# ads1115-reference_easyeda.net
KiCad netlist of a schematic drawn in EasyEDA
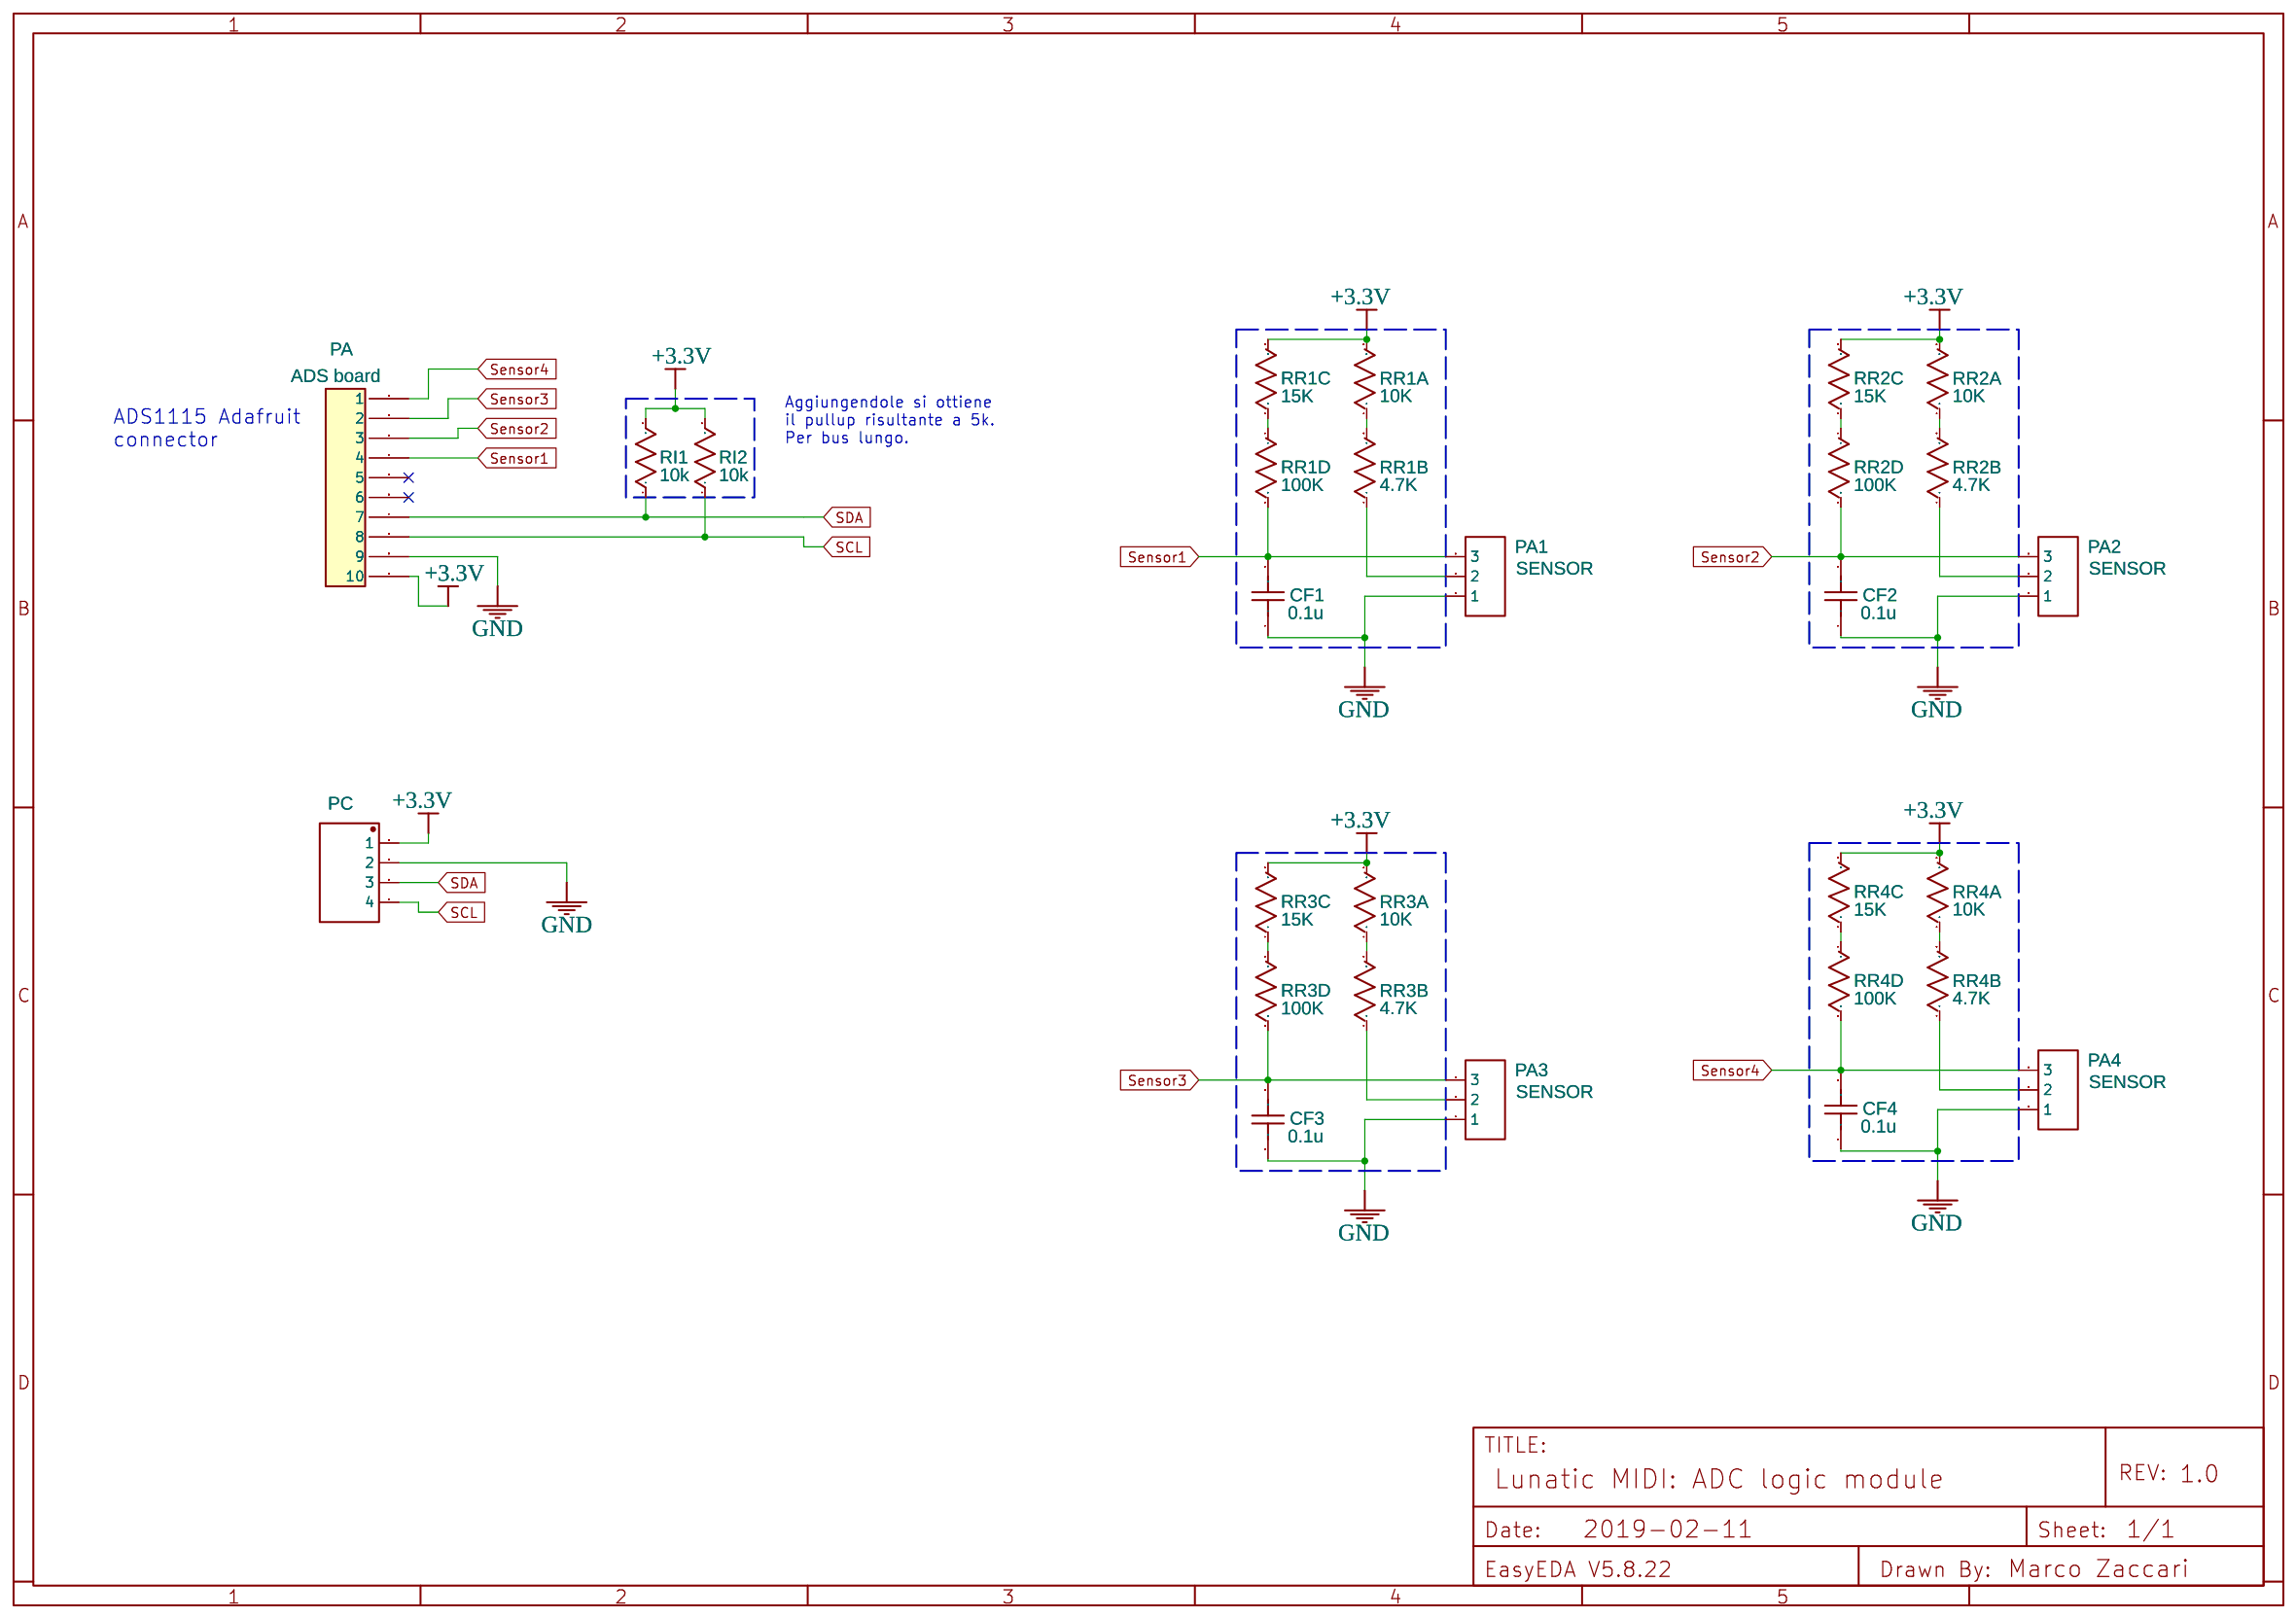
[diagram p0: ADC logic]
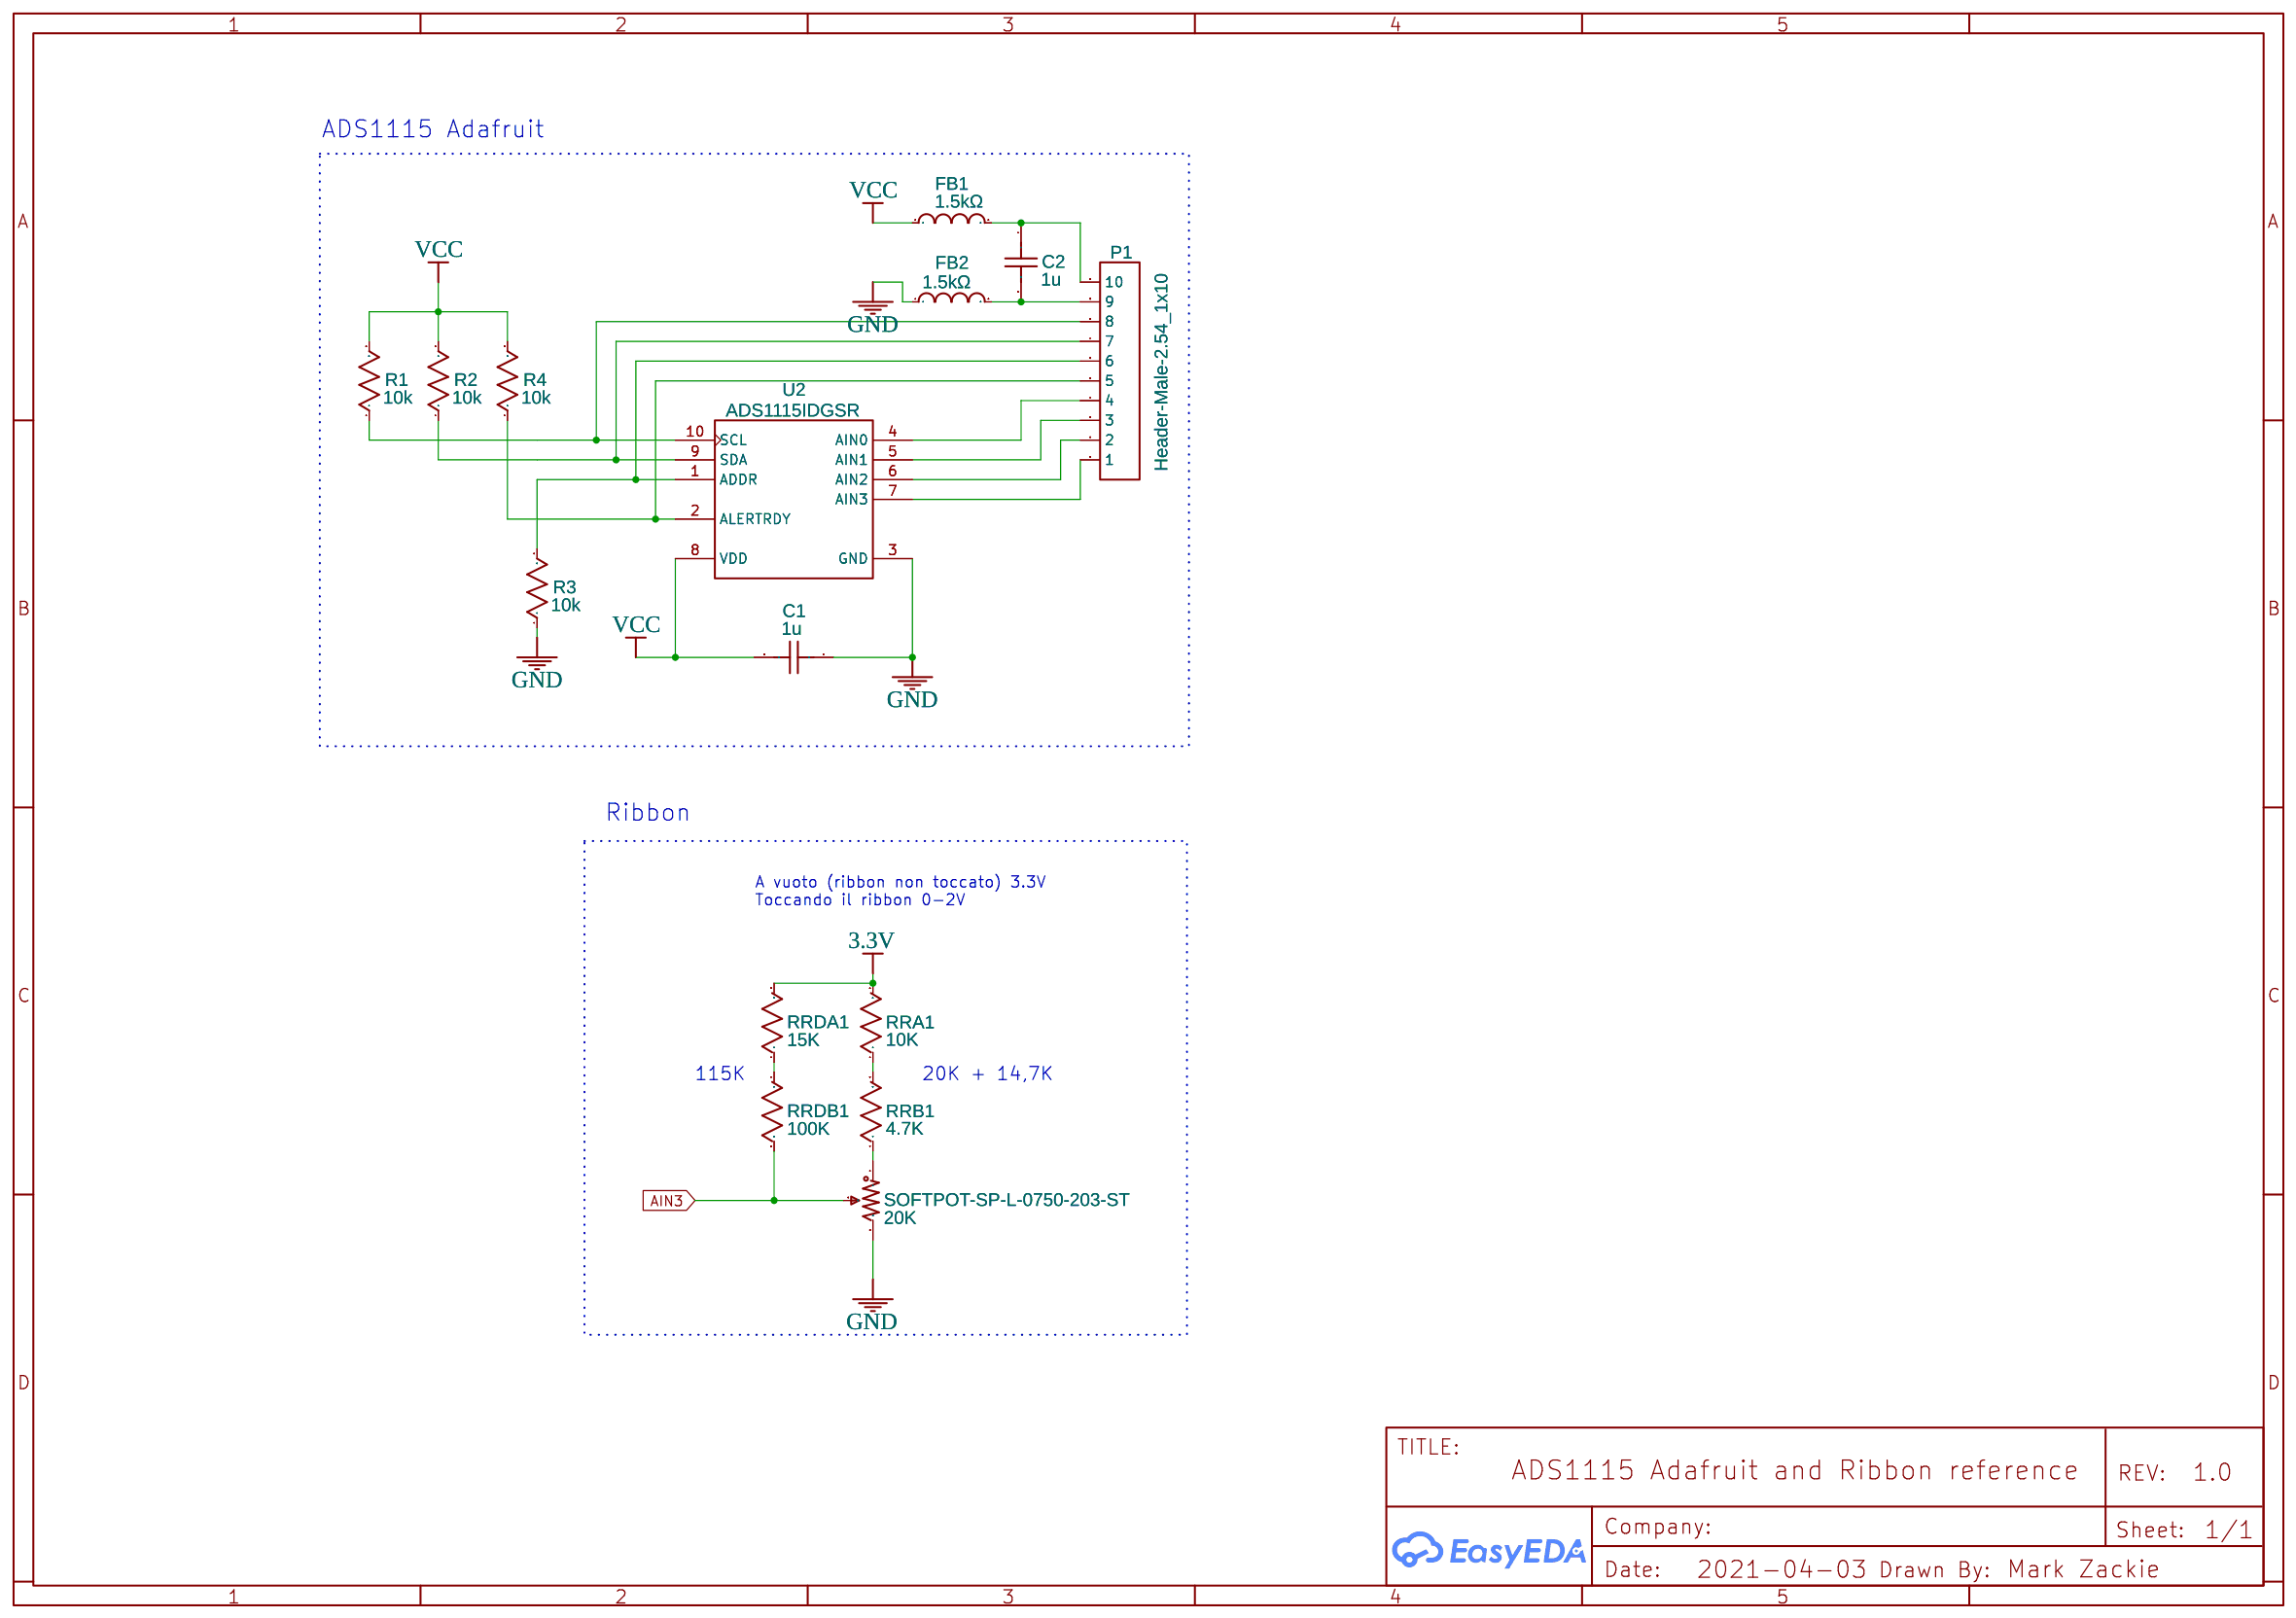
[diagram p1: ADS1115 Adafruit and Ribbon (reference)]

(export (version "E")
  (design (tool "Eeschema 10.0.6"))
  (components
    (comp (ref "CF1")
      (value "0.1u")
      (fields (field (name "BOM_Manufacturer Part") "?"))
      (libsource (lib "") (part "Cap_RAD-0.1_US"))
    )
    (comp (ref "CF2")
      (value "0.1u")
      (fields (field (name "BOM_Manufacturer Part") "?"))
      (libsource (lib "") (part "Cap_RAD-0.1_US"))
    )
    (comp (ref "CF3")
      (value "0.1u")
      (fields (field (name "BOM_Manufacturer Part") "?"))
      (libsource (lib "") (part "Cap_RAD-0.1_US"))
    )
    (comp (ref "CF4")
      (value "0.1u")
      (fields (field (name "BOM_Manufacturer Part") "?"))
      (libsource (lib "") (part "Cap_RAD-0.1_US"))
    )
    (comp (ref "PA")
      (value "ADS board")
      (fields
        (field (name "BOM_Manufacturer Part") "Header-Female-1.27_1x10")
        (field (name "BOM_Supplier Part") "C29357")
      )
      (libsource (lib "") (part "Unknown_180_240"))
    )
    (comp (ref "PA1")
      (value "SENSOR")
      (fields
        (field (name "BOM_Manufacturer Part") "Header2.54mm 1*3P")
        (field (name "BOM_Supplier Part") "C49257")
      )
      (libsource (lib "") (part "Unknown_740_285"))
    )
    (comp (ref "PA2")
      (value "SENSOR")
      (fields
        (field (name "BOM_Manufacturer Part") "Header2.54mm 1*3P")
        (field (name "BOM_Supplier Part") "C49257")
      )
      (libsource (lib "") (part "Unknown_1030_285"))
    )
    (comp (ref "PA3")
      (value "SENSOR")
      (fields
        (field (name "BOM_Manufacturer Part") "Header2.54mm 1*3P")
        (field (name "BOM_Supplier Part") "C49257")
      )
      (libsource (lib "") (part "Unknown_740_550"))
    )
    (comp (ref "PA4")
      (value "SENSOR")
      (fields
        (field (name "BOM_Manufacturer Part") "Header2.54mm 1*3P")
        (field (name "BOM_Supplier Part") "C49257")
      )
      (libsource (lib "") (part "Unknown_1030_545"))
    )
    (comp (ref "PC")
      (value "Header-Male-2.54_1x4")
      (fields
        (field (name "BOM_Manufacturer Part") "210S-1*4P L=11.6MMGold-plated black")
        (field (name "BOM_Supplier Part") "C124378")
      )
      (libsource (lib "") (part "Unknown_175_435"))
    )
    (comp (ref "RI1")
      (value "10k")
      (fields (field (name "BOM_Manufacturer Part") "?"))
      (libsource (lib "") (part "Res_AXIAL-0.3(1/8W)_US_9"))
    )
    (comp (ref "RI2")
      (value "10k")
      (fields (field (name "BOM_Manufacturer Part") "?"))
      (libsource (lib "") (part "Res_AXIAL-0.3(1/8W)_US_9"))
    )
    (comp (ref "RR1A")
      (value "10K")
      (fields (field (name "BOM_Manufacturer Part") "?"))
      (libsource (lib "") (part "Res_AXIAL-0.3(1/8W)_US_11"))
    )
    (comp (ref "RR1B")
      (value "4.7K")
      (fields (field (name "BOM_Manufacturer Part") "?"))
      (libsource (lib "") (part "Res_AXIAL-0.3(1/8W)_US_12"))
    )
    (comp (ref "RR1C")
      (value "15K")
      (fields (field (name "BOM_Manufacturer Part") "?"))
      (libsource (lib "") (part "Res_AXIAL-0.3(1/8W)_US_6"))
    )
    (comp (ref "RR1D")
      (value "100K")
      (fields (field (name "BOM_Manufacturer Part") "?"))
      (libsource (lib "") (part "Res_AXIAL-0.3(1/8W)_US_4"))
    )
    (comp (ref "RR2A")
      (value "10K")
      (fields (field (name "BOM_Manufacturer Part") "?"))
      (libsource (lib "") (part "Res_AXIAL-0.3(1/8W)_US_1"))
    )
    (comp (ref "RR2B")
      (value "4.7K")
      (fields (field (name "BOM_Manufacturer Part") "?"))
      (libsource (lib "") (part "Res_AXIAL-0.3(1/8W)_US_2"))
    )
    (comp (ref "RR2C")
      (value "15K")
      (fields (field (name "BOM_Manufacturer Part") "?"))
      (libsource (lib "") (part "Res_AXIAL-0.3(1/8W)_US_13"))
    )
    (comp (ref "RR2D")
      (value "100K")
      (fields (field (name "BOM_Manufacturer Part") "?"))
      (libsource (lib "") (part "Res_AXIAL-0.3(1/8W)_US"))
    )
    (comp (ref "RR3A")
      (value "10K")
      (fields (field (name "BOM_Manufacturer Part") "?"))
      (libsource (lib "") (part "Res_AXIAL-0.3(1/8W)_US_5"))
    )
    (comp (ref "RR3B")
      (value "4.7K")
      (fields (field (name "BOM_Manufacturer Part") "?"))
      (libsource (lib "") (part "Res_AXIAL-0.3(1/8W)_US_16"))
    )
    (comp (ref "RR3C")
      (value "15K")
      (fields (field (name "BOM_Manufacturer Part") "?"))
      (libsource (lib "") (part "Res_AXIAL-0.3(1/8W)_US_7"))
    )
    (comp (ref "RR3D")
      (value "100K")
      (fields (field (name "BOM_Manufacturer Part") "?"))
      (libsource (lib "") (part "Res_AXIAL-0.3(1/8W)_US_3"))
    )
    (comp (ref "RR4A")
      (value "10K")
      (fields (field (name "BOM_Manufacturer Part") "?"))
      (libsource (lib "") (part "Res_AXIAL-0.3(1/8W)_US_14"))
    )
    (comp (ref "RR4B")
      (value "4.7K")
      (fields (field (name "BOM_Manufacturer Part") "?"))
      (libsource (lib "") (part "Res_AXIAL-0.3(1/8W)_US_8"))
    )
    (comp (ref "RR4C")
      (value "15K")
      (fields (field (name "BOM_Manufacturer Part") "?"))
      (libsource (lib "") (part "Res_AXIAL-0.3(1/8W)_US_15"))
    )
    (comp (ref "RR4D")
      (value "100K")
      (fields (field (name "BOM_Manufacturer Part") "?"))
      (libsource (lib "") (part "Res_AXIAL-0.3(1/8W)_US_10"))
    )
    (comp (ref "C1")
      (value "1u")
      (fields (field (name "BOM_Manufacturer Part") "?"))
      (libsource (lib "") (part "Cap_RAD-0.1_US"))
    )
    (comp (ref "C2")
      (value "1u")
      (fields (field (name "BOM_Manufacturer Part") "?"))
      (libsource (lib "") (part "Cap_RAD-0.1_US_1"))
    )
    (comp (ref "FB1")
      (value "1.5kΩ")
      (fields
        (field (name "BOM_Manufacturer Part") "MMZ2012Y152B")
        (field (name "BOM_Supplier Part") "C21517")
      )
      (libsource (lib "") (part "MMZ2012Y152B"))
    )
    (comp (ref "FB2")
      (value "1.5kΩ")
      (fields
        (field (name "BOM_Manufacturer Part") "MMZ2012Y152B")
        (field (name "BOM_Supplier Part") "C21517")
      )
      (libsource (lib "") (part "MMZ2012Y152B"))
    )
    (comp (ref "P1")
      (value "Header-Male-2.54_1x10")
      (fields
        (field (name "BOM_Manufacturer Part") "Headers  Pins2.54mm1*10P")
        (field (name "BOM_Supplier Part") "C57369")
      )
      (libsource (lib "") (part "Unknown_555_-625"))
    )
    (comp (ref "R1")
      (value "10k")
      (fields (field (name "BOM_Manufacturer Part") "?"))
      (libsource (lib "") (part "Res_AXIAL-0.3(1/8W)_US"))
    )
    (comp (ref "R2")
      (value "10k")
      (fields (field (name "BOM_Manufacturer Part") "?"))
      (libsource (lib "") (part "Res_AXIAL-0.3(1/8W)_US"))
    )
    (comp (ref "R3")
      (value "10k")
      (fields (field (name "BOM_Manufacturer Part") "?"))
      (libsource (lib "") (part "Res_AXIAL-0.3(1/8W)_US"))
    )
    (comp (ref "R4")
      (value "10k")
      (fields (field (name "BOM_Manufacturer Part") "?"))
      (libsource (lib "") (part "Res_AXIAL-0.3(1/8W)_US"))
    )
    (comp (ref "RRA1")
      (value "10K")
      (fields (field (name "BOM_Manufacturer Part") "?"))
      (libsource (lib "") (part "Res_AXIAL-0.3(1/8W)_US_3"))
    )
    (comp (ref "RRB1")
      (value "4.7K")
      (fields (field (name "BOM_Manufacturer Part") "?"))
      (libsource (lib "") (part "Res_AXIAL-0.3(1/8W)_US_1"))
    )
    (comp (ref "RRDA1")
      (value "15K")
      (fields (field (name "BOM_Manufacturer Part") "?"))
      (libsource (lib "") (part "Res_AXIAL-0.3(1/8W)_US_4"))
    )
    (comp (ref "RRDB1")
      (value "100K")
      (fields (field (name "BOM_Manufacturer Part") "?"))
      (libsource (lib "") (part "Res_AXIAL-0.3(1/8W)_US_2"))
    )
    (comp (ref "SOFTPOT-SP-L-0750-203-ST")
      (value "20K")
      (fields
        (field (name "BOM_Manufacturer Part") "3386P-1-101LF")
        (field (name "BOM_Supplier Part") "C125022")
      )
      (libsource (lib "") (part "3386P-1-101LF_US"))
    )
    (comp (ref "U2")
      (value "ADS1115IDGSR")
      (fields (field (name "BOM_Supplier Part") "C37593"))
      (libsource (lib "") (part "Unknown_395_-560"))
    )
  )
  (nets
    (net (code "1") (name "+3.3V") (class "Default")
      (node (ref "PA") (pin "10") (pinfunction "10_10") (pintype "input"))
      (node (ref "PC") (pin "1") (pinfunction "1_1") (pintype "unspecified"))
      (node (ref "RI1") (pin "2") (pinfunction "2_2") (pintype "unspecified"))
      (node (ref "RI2") (pin "2") (pinfunction "2_2") (pintype "unspecified"))
      (node (ref "RR1A") (pin "2") (pinfunction "2_2") (pintype "unspecified"))
      (node (ref "RR1C") (pin "2") (pinfunction "2_2") (pintype "unspecified"))
      (node (ref "RR2A") (pin "2") (pinfunction "2_2") (pintype "unspecified"))
      (node (ref "RR2C") (pin "2") (pinfunction "2_2") (pintype "unspecified"))
      (node (ref "RR3A") (pin "2") (pinfunction "2_2") (pintype "unspecified"))
      (node (ref "RR3C") (pin "2") (pinfunction "2_2") (pintype "unspecified"))
      (node (ref "RR4A") (pin "2") (pinfunction "2_2") (pintype "unspecified"))
      (node (ref "RR4C") (pin "2") (pinfunction "2_2") (pintype "unspecified"))
    )
    (net (code "2") (name "3.3V") (class "Default")
      (node (ref "RRA1") (pin "2") (pinfunction "2_2") (pintype "unspecified"))
      (node (ref "RRDA1") (pin "2") (pinfunction "2_2") (pintype "unspecified"))
    )
    (net (code "3") (name "AIN3") (class "Default")
      (node (ref "RRDB1") (pin "2") (pinfunction "2_2") (pintype "unspecified"))
      (node (ref "SOFTPOT-SP-L-0750-203-ST") (pin "2") (pinfunction "2_2") (pintype "unspecified"))
    )
    (net (code "4") (name "GND") (class "Default")
      (node (ref "C1") (pin "1") (pinfunction "1_1") (pintype "unspecified"))
      (node (ref "CF1") (pin "1") (pinfunction "1_1") (pintype "unspecified"))
      (node (ref "CF2") (pin "1") (pinfunction "1_1") (pintype "unspecified"))
      (node (ref "CF3") (pin "1") (pinfunction "1_1") (pintype "unspecified"))
      (node (ref "CF4") (pin "1") (pinfunction "1_1") (pintype "unspecified"))
      (node (ref "FB2") (pin "1") (pinfunction "1_1") (pintype "unspecified"))
      (node (ref "PA") (pin "9") (pinfunction "9_9") (pintype "input"))
      (node (ref "PA1") (pin "1") (pinfunction "1_1") (pintype "input"))
      (node (ref "PA2") (pin "1") (pinfunction "1_1") (pintype "input"))
      (node (ref "PA3") (pin "1") (pinfunction "1_1") (pintype "input"))
      (node (ref "PA4") (pin "1") (pinfunction "1_1") (pintype "input"))
      (node (ref "PC") (pin "2") (pinfunction "2_2") (pintype "unspecified"))
      (node (ref "R3") (pin "1") (pinfunction "1_1") (pintype "unspecified"))
      (node (ref "SOFTPOT-SP-L-0750-203-ST") (pin "3") (pinfunction "3_3") (pintype "unspecified"))
      (node (ref "U2") (pin "3") (pinfunction "GND_3") (pintype "passive"))
    )
    (net (code "5") (name "Net-(C2-Pad1)") (class "Default")
      (node (ref "C2") (pin "1") (pinfunction "1_1") (pintype "unspecified"))
      (node (ref "FB1") (pin "2") (pinfunction "2_2") (pintype "unspecified"))
      (node (ref "P1") (pin "10") (pinfunction "10_10") (pintype "input"))
    )
    (net (code "6") (name "Net-(C2-Pad2)") (class "Default")
      (node (ref "C2") (pin "2") (pinfunction "2_2") (pintype "unspecified"))
      (node (ref "FB2") (pin "2") (pinfunction "2_2") (pintype "unspecified"))
      (node (ref "P1") (pin "9") (pinfunction "9_9") (pintype "input"))
    )
    (net (code "7") (name "Net-(PA1-Pad2)") (class "Default")
      (node (ref "PA1") (pin "2") (pinfunction "2_2") (pintype "input"))
      (node (ref "RR1B") (pin "1") (pinfunction "1_1") (pintype "unspecified"))
    )
    (net (code "8") (name "Net-(PA2-Pad2)") (class "Default")
      (node (ref "PA2") (pin "2") (pinfunction "2_2") (pintype "input"))
      (node (ref "RR2B") (pin "1") (pinfunction "1_1") (pintype "unspecified"))
    )
    (net (code "9") (name "Net-(PA3-Pad2)") (class "Default")
      (node (ref "PA3") (pin "2") (pinfunction "2_2") (pintype "input"))
      (node (ref "RR3B") (pin "1") (pinfunction "1_1") (pintype "unspecified"))
    )
    (net (code "10") (name "Net-(PA4-Pad2)") (class "Default")
      (node (ref "PA4") (pin "2") (pinfunction "2_2") (pintype "input"))
      (node (ref "RR4B") (pin "1") (pinfunction "1_1") (pintype "unspecified"))
    )
    (net (code "11") (name "Net-(RR1A-Pad1)") (class "Default")
      (node (ref "RR1A") (pin "1") (pinfunction "1_1") (pintype "unspecified"))
      (node (ref "RR1B") (pin "2") (pinfunction "2_2") (pintype "unspecified"))
    )
    (net (code "12") (name "Net-(RR1C-Pad1)") (class "Default")
      (node (ref "RR1C") (pin "1") (pinfunction "1_1") (pintype "unspecified"))
      (node (ref "RR1D") (pin "1") (pinfunction "1_1") (pintype "unspecified"))
    )
    (net (code "13") (name "Net-(RR2A-Pad1)") (class "Default")
      (node (ref "RR2A") (pin "1") (pinfunction "1_1") (pintype "unspecified"))
      (node (ref "RR2B") (pin "2") (pinfunction "2_2") (pintype "unspecified"))
    )
    (net (code "14") (name "Net-(RR2C-Pad1)") (class "Default")
      (node (ref "RR2C") (pin "1") (pinfunction "1_1") (pintype "unspecified"))
      (node (ref "RR2D") (pin "1") (pinfunction "1_1") (pintype "unspecified"))
    )
    (net (code "15") (name "Net-(RR3A-Pad1)") (class "Default")
      (node (ref "RR3A") (pin "1") (pinfunction "1_1") (pintype "unspecified"))
      (node (ref "RR3B") (pin "2") (pinfunction "2_2") (pintype "unspecified"))
    )
    (net (code "16") (name "Net-(RR3C-Pad1)") (class "Default")
      (node (ref "RR3C") (pin "1") (pinfunction "1_1") (pintype "unspecified"))
      (node (ref "RR3D") (pin "1") (pinfunction "1_1") (pintype "unspecified"))
    )
    (net (code "17") (name "Net-(RR4A-Pad1)") (class "Default")
      (node (ref "RR4A") (pin "1") (pinfunction "1_1") (pintype "unspecified"))
      (node (ref "RR4B") (pin "2") (pinfunction "2_2") (pintype "unspecified"))
    )
    (net (code "18") (name "Net-(RR4C-Pad1)") (class "Default")
      (node (ref "RR4C") (pin "1") (pinfunction "1_1") (pintype "unspecified"))
      (node (ref "RR4D") (pin "1") (pinfunction "1_1") (pintype "unspecified"))
    )
    (net (code "19") (name "Net-(RRA1-Pad1)") (class "Default")
      (node (ref "RRA1") (pin "1") (pinfunction "1_1") (pintype "unspecified"))
      (node (ref "RRB1") (pin "2") (pinfunction "2_2") (pintype "unspecified"))
    )
    (net (code "20") (name "Net-(RRB1-Pad1)") (class "Default")
      (node (ref "RRB1") (pin "1") (pinfunction "1_1") (pintype "unspecified"))
      (node (ref "SOFTPOT-SP-L-0750-203-ST") (pin "1") (pinfunction "1_1") (pintype "unspecified"))
    )
    (net (code "21") (name "Net-(RRDA1-Pad1)") (class "Default")
      (node (ref "RRDA1") (pin "1") (pinfunction "1_1") (pintype "unspecified"))
      (node (ref "RRDB1") (pin "1") (pinfunction "1_1") (pintype "unspecified"))
    )
    (net (code "22") (name "Net-(U2-ADDR)") (class "Default")
      (node (ref "P1") (pin "6") (pinfunction "6_6") (pintype "input"))
      (node (ref "R3") (pin "2") (pinfunction "2_2") (pintype "unspecified"))
      (node (ref "U2") (pin "1") (pinfunction "ADDR_1") (pintype "unspecified"))
    )
    (net (code "23") (name "Net-(U2-AIN0)") (class "Default")
      (node (ref "P1") (pin "4") (pinfunction "4_4") (pintype "input"))
      (node (ref "U2") (pin "4") (pinfunction "AIN0_4") (pintype "unspecified"))
    )
    (net (code "24") (name "Net-(U2-AIN1)") (class "Default")
      (node (ref "P1") (pin "3") (pinfunction "3_3") (pintype "input"))
      (node (ref "U2") (pin "5") (pinfunction "AIN1_5") (pintype "unspecified"))
    )
    (net (code "25") (name "Net-(U2-AIN2)") (class "Default")
      (node (ref "P1") (pin "2") (pinfunction "2_2") (pintype "input"))
      (node (ref "U2") (pin "6") (pinfunction "AIN2_6") (pintype "unspecified"))
    )
    (net (code "26") (name "Net-(U2-AIN3)") (class "Default")
      (node (ref "P1") (pin "1") (pinfunction "1_1") (pintype "input"))
      (node (ref "U2") (pin "7") (pinfunction "AIN3_7") (pintype "unspecified"))
    )
    (net (code "27") (name "Net-(U2-ALERTRDY)") (class "Default")
      (node (ref "P1") (pin "5") (pinfunction "5_5") (pintype "input"))
      (node (ref "R4") (pin "1") (pinfunction "1_1") (pintype "unspecified"))
      (node (ref "U2") (pin "2") (pinfunction "ALERTRDY_2") (pintype "unspecified"))
    )
    (net (code "28") (name "Net-(U2-SCL)") (class "Default")
      (node (ref "P1") (pin "8") (pinfunction "8_8") (pintype "input"))
      (node (ref "R1") (pin "1") (pinfunction "1_1") (pintype "unspecified"))
      (node (ref "U2") (pin "10") (pinfunction "SCL_10") (pintype "unspecified"))
    )
    (net (code "29") (name "Net-(U2-SDA)") (class "Default")
      (node (ref "P1") (pin "7") (pinfunction "7_7") (pintype "input"))
      (node (ref "R2") (pin "1") (pinfunction "1_1") (pintype "unspecified"))
      (node (ref "U2") (pin "9") (pinfunction "SDA_9") (pintype "bidirectional"))
    )
    (net (code "30") (name "SCL") (class "Default")
      (node (ref "PA") (pin "8") (pinfunction "8_8") (pintype "input"))
      (node (ref "PC") (pin "4") (pinfunction "4_4") (pintype "unspecified"))
      (node (ref "RI2") (pin "1") (pinfunction "1_1") (pintype "unspecified"))
    )
    (net (code "31") (name "SDA") (class "Default")
      (node (ref "PA") (pin "7") (pinfunction "7_7") (pintype "input"))
      (node (ref "PC") (pin "3") (pinfunction "3_3") (pintype "unspecified"))
      (node (ref "RI1") (pin "1") (pinfunction "1_1") (pintype "unspecified"))
    )
    (net (code "32") (name "Sensor1") (class "Default")
      (node (ref "CF1") (pin "2") (pinfunction "2_2") (pintype "unspecified"))
      (node (ref "PA") (pin "4") (pinfunction "4_4") (pintype "input"))
      (node (ref "PA1") (pin "3") (pinfunction "3_3") (pintype "input"))
      (node (ref "RR1D") (pin "2") (pinfunction "2_2") (pintype "unspecified"))
    )
    (net (code "33") (name "Sensor2") (class "Default")
      (node (ref "CF2") (pin "2") (pinfunction "2_2") (pintype "unspecified"))
      (node (ref "PA") (pin "3") (pinfunction "3_3") (pintype "input"))
      (node (ref "PA2") (pin "3") (pinfunction "3_3") (pintype "input"))
      (node (ref "RR2D") (pin "2") (pinfunction "2_2") (pintype "unspecified"))
    )
    (net (code "34") (name "Sensor3") (class "Default")
      (node (ref "CF3") (pin "2") (pinfunction "2_2") (pintype "unspecified"))
      (node (ref "PA") (pin "2") (pinfunction "2_2") (pintype "input"))
      (node (ref "PA3") (pin "3") (pinfunction "3_3") (pintype "input"))
      (node (ref "RR3D") (pin "2") (pinfunction "2_2") (pintype "unspecified"))
    )
    (net (code "35") (name "Sensor4") (class "Default")
      (node (ref "CF4") (pin "2") (pinfunction "2_2") (pintype "unspecified"))
      (node (ref "PA") (pin "1") (pinfunction "1_1") (pintype "input"))
      (node (ref "PA4") (pin "3") (pinfunction "3_3") (pintype "input"))
      (node (ref "RR4D") (pin "2") (pinfunction "2_2") (pintype "unspecified"))
    )
    (net (code "36") (name "VCC") (class "Default")
      (node (ref "C1") (pin "2") (pinfunction "2_2") (pintype "unspecified"))
      (node (ref "FB1") (pin "1") (pinfunction "1_1") (pintype "unspecified"))
      (node (ref "R1") (pin "2") (pinfunction "2_2") (pintype "unspecified"))
      (node (ref "R2") (pin "2") (pinfunction "2_2") (pintype "unspecified"))
      (node (ref "R4") (pin "2") (pinfunction "2_2") (pintype "unspecified"))
      (node (ref "U2") (pin "8") (pinfunction "VDD_8") (pintype "passive"))
    )
    (net (code "37") (name "unconnected-(PA-Pad5)") (class "Default")
      (node (ref "PA") (pin "5") (pinfunction "5_5") (pintype "input+no_connect"))
    )
    (net (code "38") (name "unconnected-(PA-Pad6)") (class "Default")
      (node (ref "PA") (pin "6") (pinfunction "6_6") (pintype "input+no_connect"))
    )
  )
)
